# ARE_adaptadora_PIC_40pin.net
KiCad netlist of a schematic drawn in EAGLE
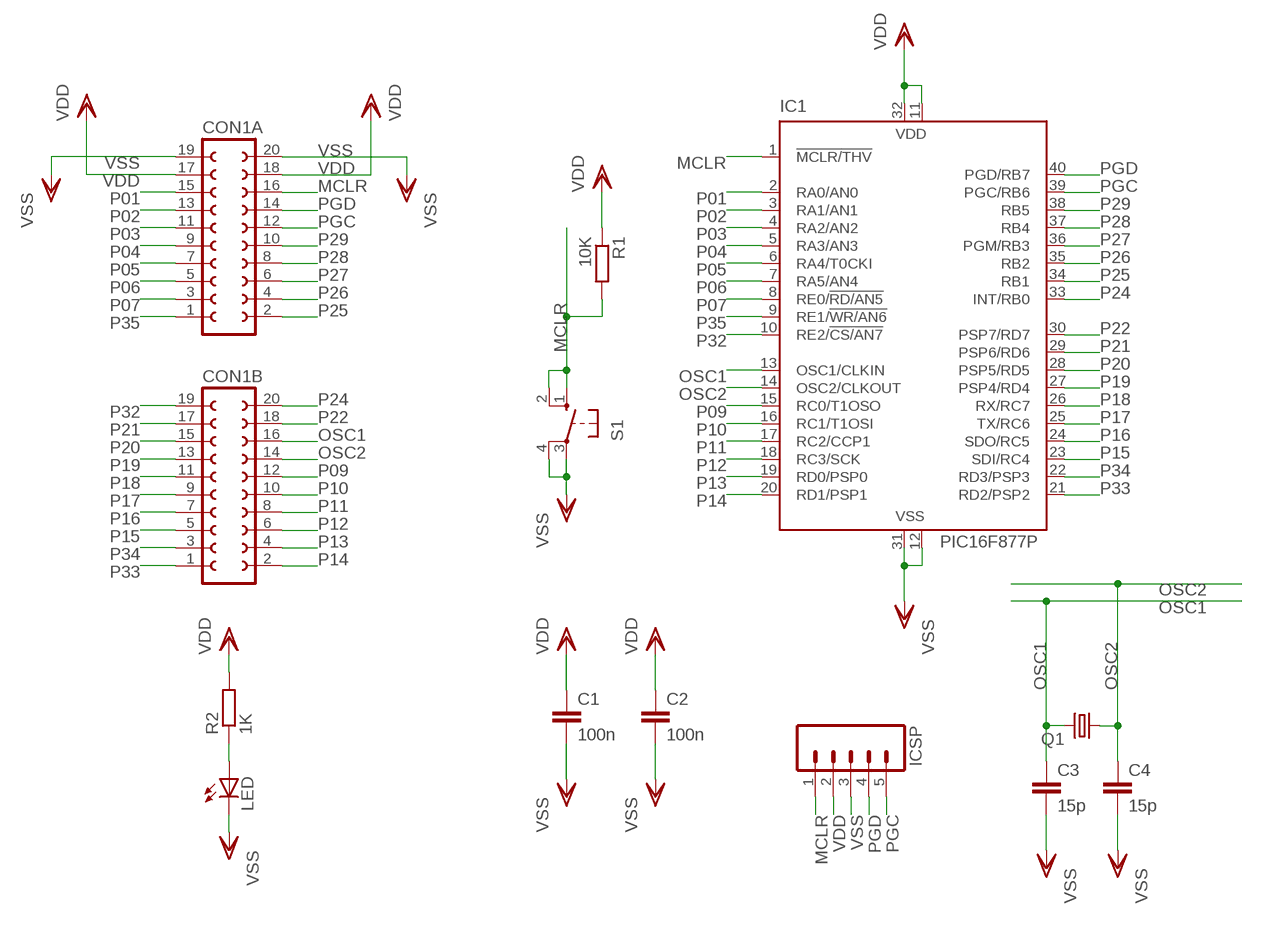
[diagram p0: schematic, sheet 1]

(export (version "E")
  (design (tool "Eeschema 10.0.6"))
  (components
    (comp (ref "C1")
      (value "100n")
      (footprint "eagle-import:C0805")
      (libsource (lib "eagle-import") (part "C-EUC0805"))
    )
    (comp (ref "C2")
      (value "100n")
      (footprint "eagle-import:C0805")
      (libsource (lib "eagle-import") (part "C-EUC0805"))
    )
    (comp (ref "C3")
      (value "15p")
      (footprint "eagle-import:C0805")
      (libsource (lib "eagle-import") (part "C-EUC0805"))
    )
    (comp (ref "C4")
      (value "15p")
      (footprint "eagle-import:C0805")
      (libsource (lib "eagle-import") (part "C-EUC0805"))
    )
    (comp (ref "CON1A")
      (value "FE10-2W")
      (footprint "eagle-import:FE10-2W")
      (fields (field (name "OC_FARNELL") "unknown") (field (name "OC_NEWARK") "unknown"))
      (libsource (lib "eagle-import") (part "FE10-2W"))
    )
    (comp (ref "CON1B")
      (value "FE10-2W")
      (footprint "eagle-import:FE10-2W")
      (libsource (lib "eagle-import") (part "FE10-2W"))
    )
    (comp (ref "IC1")
      (value "PIC16F877P")
      (footprint "eagle-import:DIL40")
      (libsource (lib "eagle-import") (part "PIC16F87P7"))
    )
    (comp (ref "ICSP")
      (value "M05PTH")
      (footprint "eagle-import:1X05")
      (libsource (lib "eagle-import") (part "M05PTH"))
    )
    (comp (ref "LED")
      (value "LED3MM")
      (footprint "eagle-import:LED3MM")
      (libsource (lib "eagle-import") (part "LED3MM"))
    )
    (comp (ref "Q1")
      (value "CRYSTALHC18U-V")
      (footprint "eagle-import:HC18U-V")
      (libsource (lib "eagle-import") (part "CRYSTALHC18U-V"))
    )
    (comp (ref "R1")
      (value "10K")
      (footprint "eagle-import:R0805")
      (libsource (lib "eagle-import") (part "R-EU_R0805"))
    )
    (comp (ref "R2")
      (value "1K")
      (footprint "eagle-import:R0805")
      (libsource (lib "eagle-import") (part "R-EU_R0805"))
    )
    (comp (ref "S1")
      (value "10-XX")
      (footprint "eagle-import:B3F-10XX")
      (fields
        (field (name "MPN") "B3F-1000")
        (field (name "MPN_1") "B3F-1000")
        (field (name "OC_FARNELL") "176432")
        (field (name "OC_NEWARK") "36M3542")
      )
      (libsource (lib "eagle-import") (part "10-XX"))
    )
  )
  (nets
    (net (code "1") (name "/MCLR") (class "Default")
      (node (ref "CON1A") (pin "16") (pinfunction "16_16") (pintype "passive"))
      (node (ref "IC1") (pin "1") (pinfunction "~{MCLR/THV}_1") (pintype "input"))
      (node (ref "ICSP") (pin "1") (pinfunction "1_1") (pintype "passive"))
      (node (ref "R1") (pin "2") (pinfunction "2_2") (pintype "passive"))
      (node (ref "S1") (pin "1") (pinfunction "S_1") (pintype "passive"))
      (node (ref "S1") (pin "2") (pinfunction "S1_2") (pintype "passive"))
    )
    (net (code "2") (name "/OSC1") (class "Default")
      (node (ref "C3") (pin "1") (pinfunction "1_1") (pintype "passive"))
      (node (ref "CON1B") (pin "16") (pinfunction "16_16") (pintype "passive"))
      (node (ref "IC1") (pin "13") (pinfunction "OSC1/CLKIN_13") (pintype "input"))
      (node (ref "Q1") (pin "2") (pinfunction "2_2") (pintype "passive"))
    )
    (net (code "3") (name "/OSC2") (class "Default")
      (node (ref "C4") (pin "1") (pinfunction "1_1") (pintype "passive"))
      (node (ref "CON1B") (pin "14") (pinfunction "14_14") (pintype "passive"))
      (node (ref "IC1") (pin "14") (pinfunction "OSC2/CLKOUT_14") (pintype "output"))
      (node (ref "Q1") (pin "1") (pinfunction "1_1") (pintype "passive"))
    )
    (net (code "4") (name "/P01") (class "Default")
      (node (ref "CON1A") (pin "15") (pinfunction "15_15") (pintype "passive"))
      (node (ref "IC1") (pin "2") (pinfunction "RA0/AN0_2") (pintype "bidirectional"))
    )
    (net (code "5") (name "/P02") (class "Default")
      (node (ref "CON1A") (pin "13") (pinfunction "13_13") (pintype "passive"))
      (node (ref "IC1") (pin "3") (pinfunction "RA1/AN1_3") (pintype "bidirectional"))
    )
    (net (code "6") (name "/P03") (class "Default")
      (node (ref "CON1A") (pin "11") (pinfunction "11_11") (pintype "passive"))
      (node (ref "IC1") (pin "4") (pinfunction "RA2/AN2_4") (pintype "bidirectional"))
    )
    (net (code "7") (name "/P04") (class "Default")
      (node (ref "CON1A") (pin "9") (pinfunction "9_9") (pintype "passive"))
      (node (ref "IC1") (pin "5") (pinfunction "RA3/AN3_5") (pintype "bidirectional"))
    )
    (net (code "8") (name "/P05") (class "Default")
      (node (ref "CON1A") (pin "7") (pinfunction "7_7") (pintype "passive"))
      (node (ref "IC1") (pin "6") (pinfunction "RA4/T0CKI_6") (pintype "bidirectional"))
    )
    (net (code "9") (name "/P06") (class "Default")
      (node (ref "CON1A") (pin "5") (pinfunction "5_5") (pintype "passive"))
      (node (ref "IC1") (pin "7") (pinfunction "RA5/AN4_7") (pintype "bidirectional"))
    )
    (net (code "10") (name "/P07") (class "Default")
      (node (ref "CON1A") (pin "3") (pinfunction "3_3") (pintype "passive"))
      (node (ref "IC1") (pin "8") (pinfunction "RE0/~{RD/AN5}_8") (pintype "bidirectional"))
    )
    (net (code "11") (name "/P09") (class "Default")
      (node (ref "CON1B") (pin "12") (pinfunction "12_12") (pintype "passive"))
      (node (ref "IC1") (pin "15") (pinfunction "RC0/T1OSO_15") (pintype "bidirectional"))
    )
    (net (code "12") (name "/P10") (class "Default")
      (node (ref "CON1B") (pin "10") (pinfunction "10_10") (pintype "passive"))
      (node (ref "IC1") (pin "16") (pinfunction "RC1/T1OSI_16") (pintype "bidirectional"))
    )
    (net (code "13") (name "/P11") (class "Default")
      (node (ref "CON1B") (pin "8") (pinfunction "8_8") (pintype "passive"))
      (node (ref "IC1") (pin "17") (pinfunction "RC2/CCP1_17") (pintype "bidirectional"))
    )
    (net (code "14") (name "/P12") (class "Default")
      (node (ref "CON1B") (pin "6") (pinfunction "6_6") (pintype "passive"))
      (node (ref "IC1") (pin "18") (pinfunction "RC3/SCK_18") (pintype "bidirectional"))
    )
    (net (code "15") (name "/P13") (class "Default")
      (node (ref "CON1B") (pin "4") (pinfunction "4_4") (pintype "passive"))
      (node (ref "IC1") (pin "19") (pinfunction "RD0/PSP0_19") (pintype "bidirectional"))
    )
    (net (code "16") (name "/P14") (class "Default")
      (node (ref "CON1B") (pin "2") (pinfunction "2_2") (pintype "passive"))
      (node (ref "IC1") (pin "20") (pinfunction "RD1/PSP1_20") (pintype "bidirectional"))
    )
    (net (code "17") (name "/P15") (class "Default")
      (node (ref "CON1B") (pin "5") (pinfunction "5_5") (pintype "passive"))
      (node (ref "IC1") (pin "23") (pinfunction "SDI/RC4_23") (pintype "bidirectional"))
    )
    (net (code "18") (name "/P16") (class "Default")
      (node (ref "CON1B") (pin "7") (pinfunction "7_7") (pintype "passive"))
      (node (ref "IC1") (pin "24") (pinfunction "SDO/RC5_24") (pintype "bidirectional"))
    )
    (net (code "19") (name "/P17") (class "Default")
      (node (ref "CON1B") (pin "9") (pinfunction "9_9") (pintype "passive"))
      (node (ref "IC1") (pin "25") (pinfunction "TX/RC6_25") (pintype "bidirectional"))
    )
    (net (code "20") (name "/P18") (class "Default")
      (node (ref "CON1B") (pin "11") (pinfunction "11_11") (pintype "passive"))
      (node (ref "IC1") (pin "26") (pinfunction "RX/RC7_26") (pintype "bidirectional"))
    )
    (net (code "21") (name "/P19") (class "Default")
      (node (ref "CON1B") (pin "13") (pinfunction "13_13") (pintype "passive"))
      (node (ref "IC1") (pin "27") (pinfunction "PSP4/RD4_27") (pintype "bidirectional"))
    )
    (net (code "22") (name "/P20") (class "Default")
      (node (ref "CON1B") (pin "15") (pinfunction "15_15") (pintype "passive"))
      (node (ref "IC1") (pin "28") (pinfunction "PSP5/RD5_28") (pintype "bidirectional"))
    )
    (net (code "23") (name "/P21") (class "Default")
      (node (ref "CON1B") (pin "17") (pinfunction "17_17") (pintype "passive"))
      (node (ref "IC1") (pin "29") (pinfunction "PSP6/RD6_29") (pintype "bidirectional"))
    )
    (net (code "24") (name "/P22") (class "Default")
      (node (ref "CON1B") (pin "18") (pinfunction "18_18") (pintype "passive"))
      (node (ref "IC1") (pin "30") (pinfunction "PSP7/RD7_30") (pintype "bidirectional"))
    )
    (net (code "25") (name "/P24") (class "Default")
      (node (ref "CON1B") (pin "20") (pinfunction "20_20") (pintype "passive"))
      (node (ref "IC1") (pin "33") (pinfunction "INT/RB0_33") (pintype "bidirectional"))
    )
    (net (code "26") (name "/P25") (class "Default")
      (node (ref "CON1A") (pin "2") (pinfunction "2_2") (pintype "passive"))
      (node (ref "IC1") (pin "34") (pinfunction "RB1_34") (pintype "bidirectional"))
    )
    (net (code "27") (name "/P26") (class "Default")
      (node (ref "CON1A") (pin "4") (pinfunction "4_4") (pintype "passive"))
      (node (ref "IC1") (pin "35") (pinfunction "RB2_35") (pintype "bidirectional"))
    )
    (net (code "28") (name "/P27") (class "Default")
      (node (ref "CON1A") (pin "6") (pinfunction "6_6") (pintype "passive"))
      (node (ref "IC1") (pin "36") (pinfunction "PGM/RB3_36") (pintype "bidirectional"))
    )
    (net (code "29") (name "/P28") (class "Default")
      (node (ref "CON1A") (pin "8") (pinfunction "8_8") (pintype "passive"))
      (node (ref "IC1") (pin "37") (pinfunction "RB4_37") (pintype "bidirectional"))
    )
    (net (code "30") (name "/P29") (class "Default")
      (node (ref "CON1A") (pin "10") (pinfunction "10_10") (pintype "passive"))
      (node (ref "IC1") (pin "38") (pinfunction "RB5_38") (pintype "bidirectional"))
    )
    (net (code "31") (name "/P32") (class "Default")
      (node (ref "CON1B") (pin "19") (pinfunction "19_19") (pintype "passive"))
      (node (ref "IC1") (pin "10") (pinfunction "RE2/~{CS/AN7}_10") (pintype "bidirectional"))
    )
    (net (code "32") (name "/P33") (class "Default")
      (node (ref "CON1B") (pin "1") (pinfunction "1_1") (pintype "passive"))
      (node (ref "IC1") (pin "21") (pinfunction "RD2/PSP2_21") (pintype "bidirectional"))
    )
    (net (code "33") (name "/P34") (class "Default")
      (node (ref "CON1B") (pin "3") (pinfunction "3_3") (pintype "passive"))
      (node (ref "IC1") (pin "22") (pinfunction "RD3/PSP3_22") (pintype "bidirectional"))
    )
    (net (code "34") (name "/P35") (class "Default")
      (node (ref "CON1A") (pin "1") (pinfunction "1_1") (pintype "passive"))
      (node (ref "IC1") (pin "9") (pinfunction "RE1/~{WR/AN6}_9") (pintype "bidirectional"))
    )
    (net (code "35") (name "/PGC") (class "Default")
      (node (ref "CON1A") (pin "12") (pinfunction "12_12") (pintype "passive"))
      (node (ref "IC1") (pin "39") (pinfunction "PGC/RB6_39") (pintype "bidirectional"))
      (node (ref "ICSP") (pin "5") (pinfunction "5_5") (pintype "passive"))
    )
    (net (code "36") (name "/PGD") (class "Default")
      (node (ref "CON1A") (pin "14") (pinfunction "14_14") (pintype "passive"))
      (node (ref "IC1") (pin "40") (pinfunction "PGD/RB7_40") (pintype "bidirectional"))
      (node (ref "ICSP") (pin "4") (pinfunction "4_4") (pintype "passive"))
    )
    (net (code "37") (name "Net-(LED-PadA)") (class "Default")
      (node (ref "LED") (pin "A") (pinfunction "A_A") (pintype "passive"))
      (node (ref "R2") (pin "1") (pinfunction "1_1") (pintype "passive"))
    )
    (net (code "38") (name "VDD") (class "Default")
      (node (ref "C1") (pin "1") (pinfunction "1_1") (pintype "passive"))
      (node (ref "C2") (pin "1") (pinfunction "1_1") (pintype "passive"))
      (node (ref "CON1A") (pin "17") (pinfunction "17_17") (pintype "passive"))
      (node (ref "CON1A") (pin "18") (pinfunction "18_18") (pintype "passive"))
      (node (ref "IC1") (pin "11") (pinfunction "VDD_11") (pintype "power_in"))
      (node (ref "IC1") (pin "32") (pinfunction "VDD_32") (pintype "power_in"))
      (node (ref "ICSP") (pin "2") (pinfunction "2_2") (pintype "passive"))
      (node (ref "R1") (pin "1") (pinfunction "1_1") (pintype "passive"))
      (node (ref "R2") (pin "2") (pinfunction "2_2") (pintype "passive"))
    )
    (net (code "39") (name "VSS") (class "Default")
      (node (ref "C1") (pin "2") (pinfunction "2_2") (pintype "passive"))
      (node (ref "C2") (pin "2") (pinfunction "2_2") (pintype "passive"))
      (node (ref "C3") (pin "2") (pinfunction "2_2") (pintype "passive"))
      (node (ref "C4") (pin "2") (pinfunction "2_2") (pintype "passive"))
      (node (ref "CON1A") (pin "19") (pinfunction "19_19") (pintype "passive"))
      (node (ref "CON1A") (pin "20") (pinfunction "20_20") (pintype "passive"))
      (node (ref "IC1") (pin "12") (pinfunction "VSS_12") (pintype "power_in"))
      (node (ref "IC1") (pin "31") (pinfunction "VSS_31") (pintype "power_in"))
      (node (ref "ICSP") (pin "3") (pinfunction "3_3") (pintype "passive"))
      (node (ref "LED") (pin "K") (pinfunction "C_K") (pintype "passive"))
      (node (ref "S1") (pin "3") (pinfunction "P_3") (pintype "passive"))
      (node (ref "S1") (pin "4") (pinfunction "P1_4") (pintype "passive"))
    )
  )
)
